# cyclops_r2b.net
KiCad netlist of a schematic drawn in EAGLE
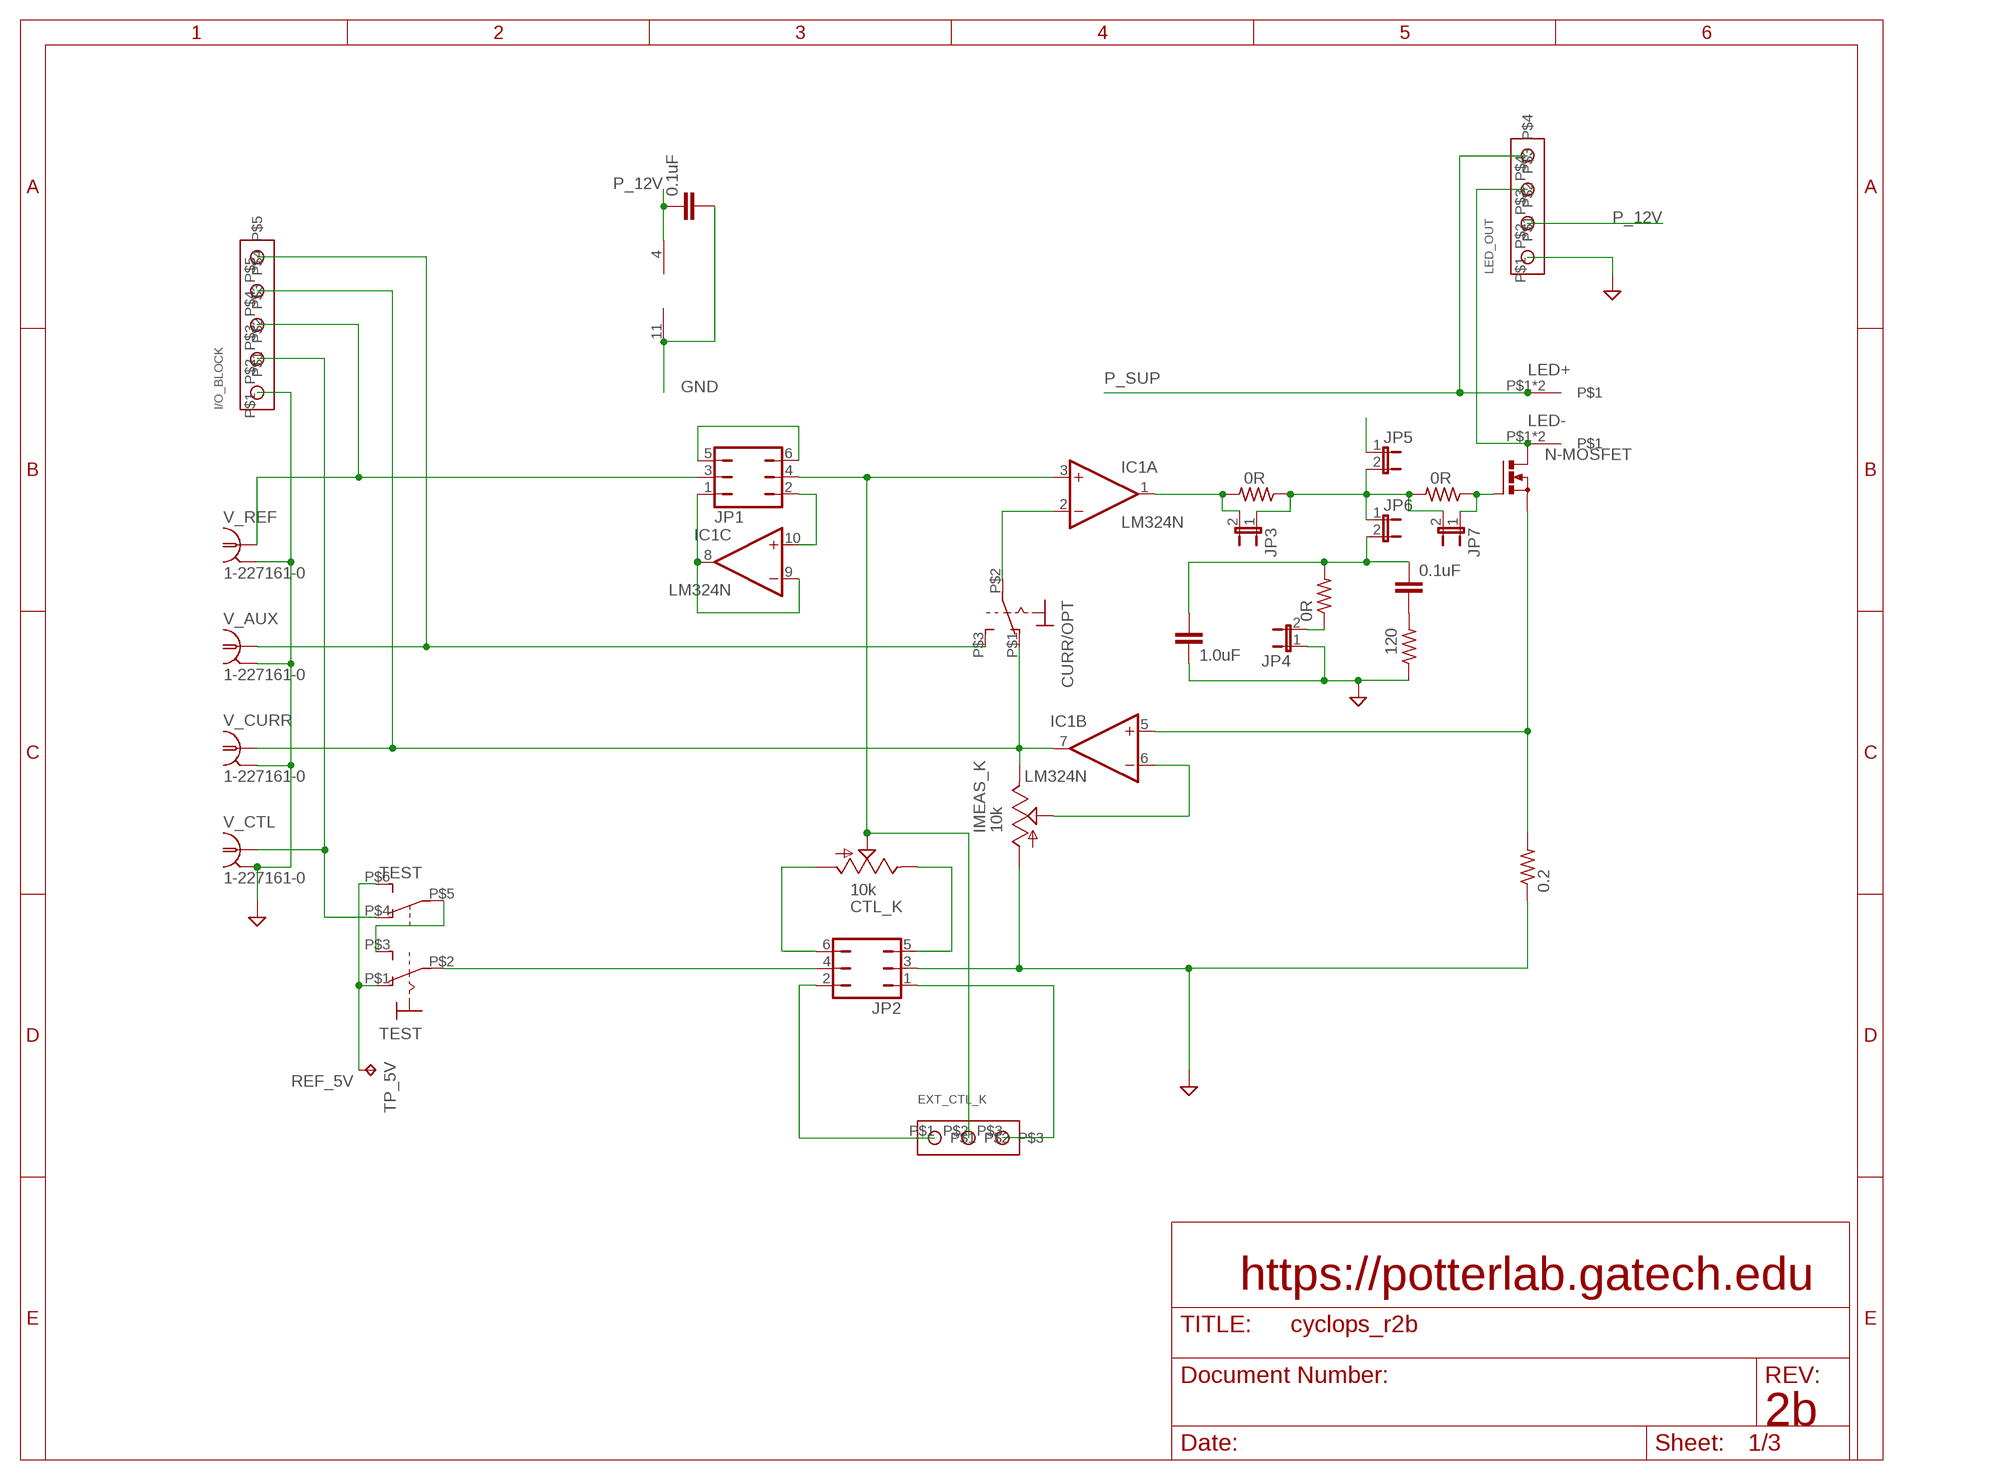
[diagram p0: schematic, sheet 1]
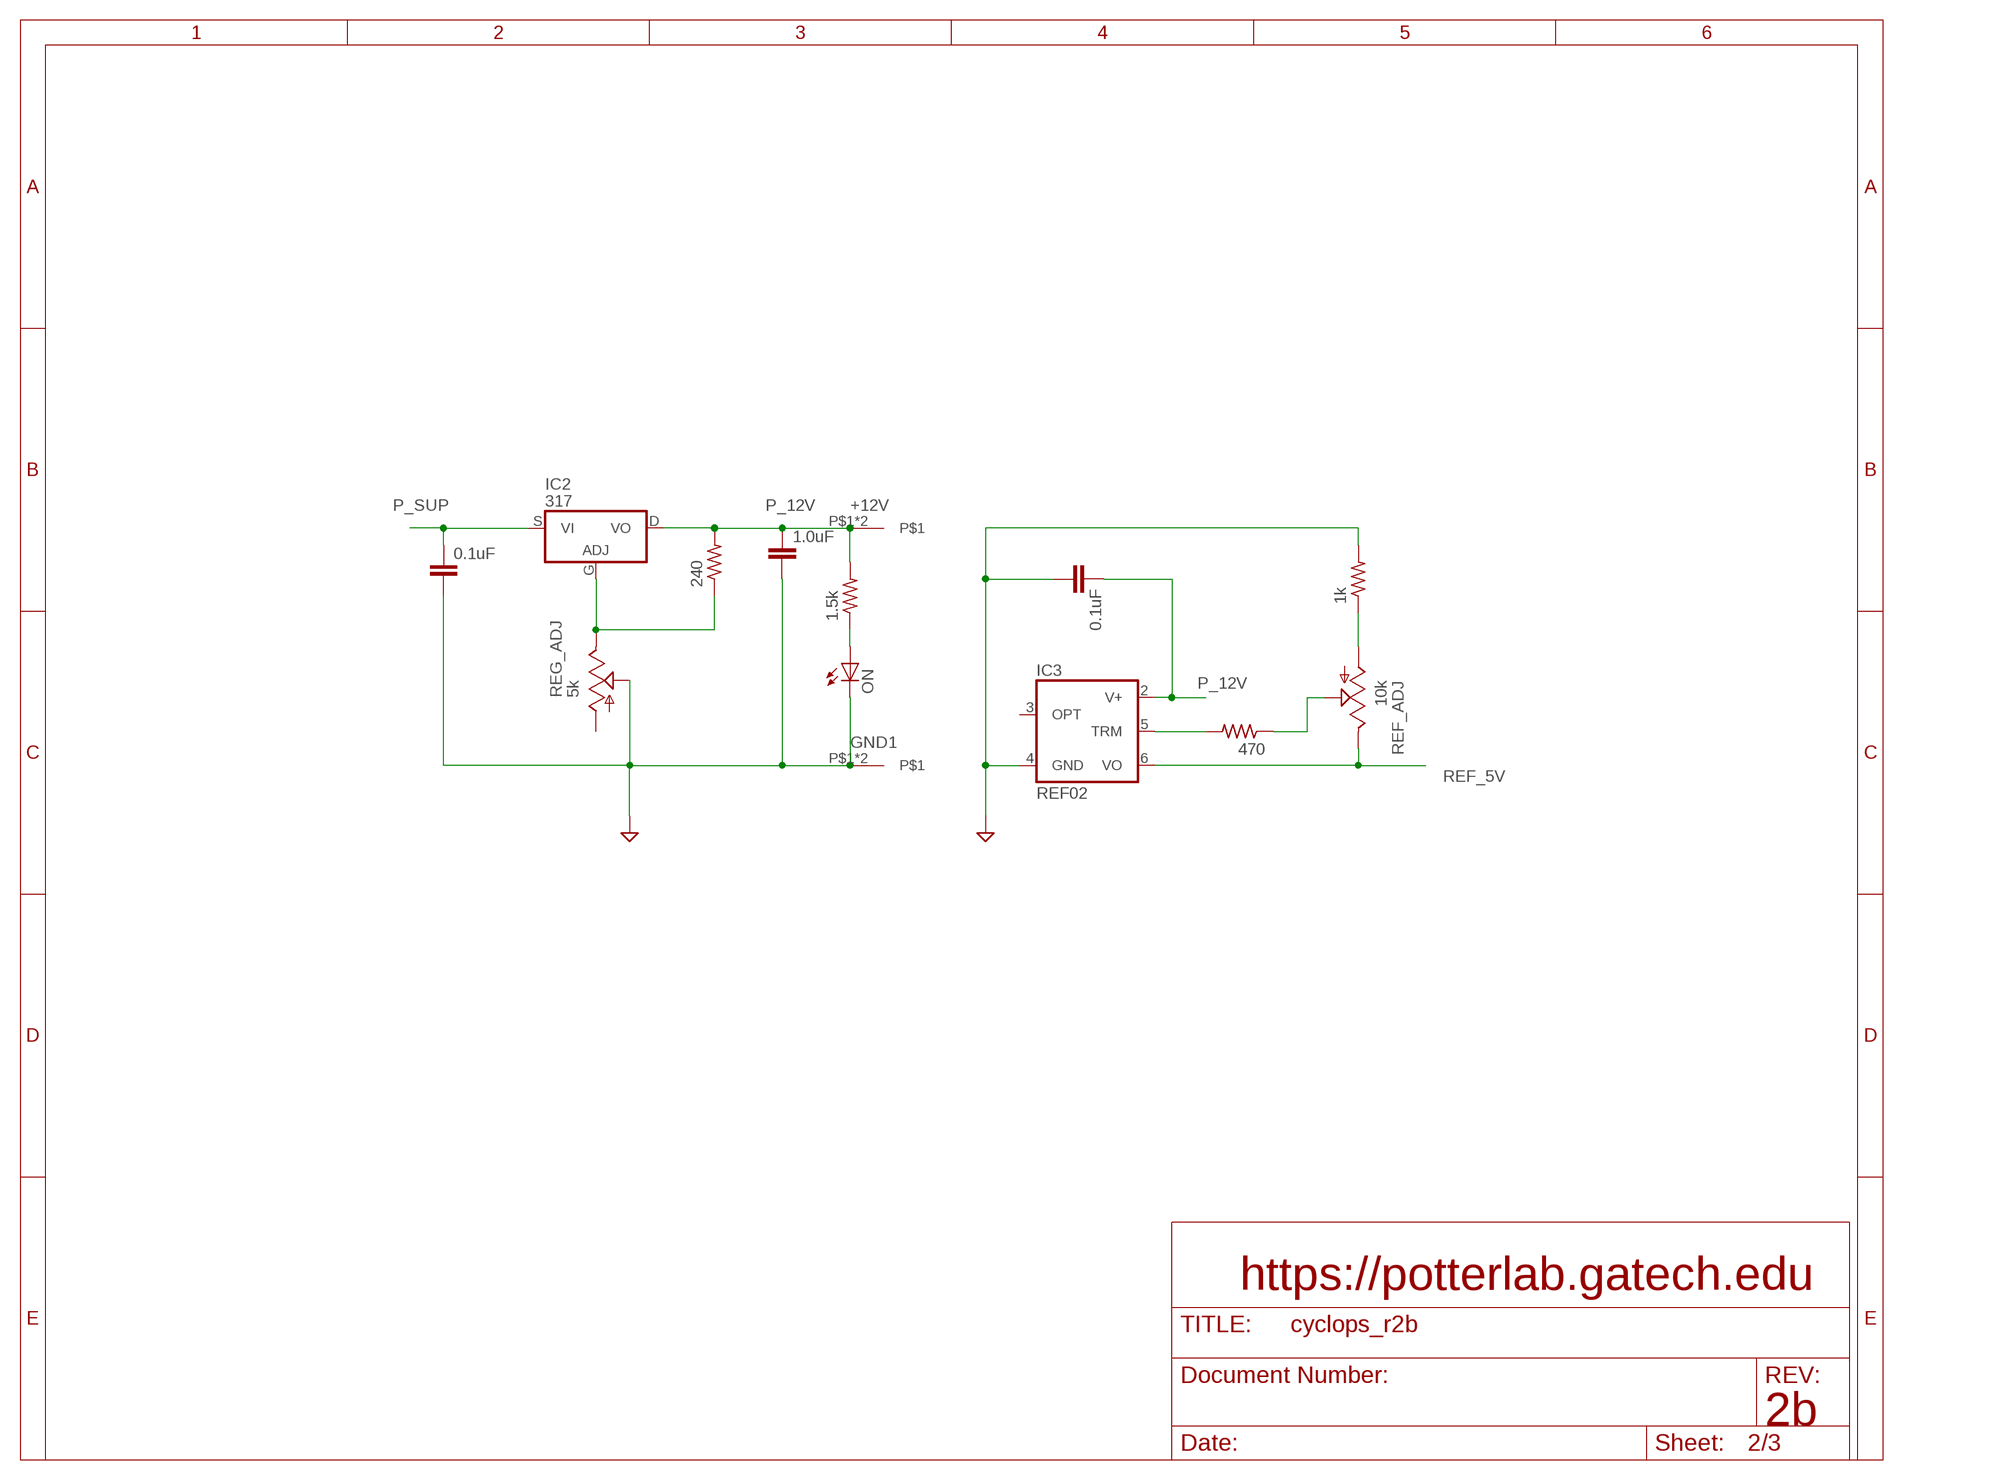
[diagram p1: schematic, sheet 2]
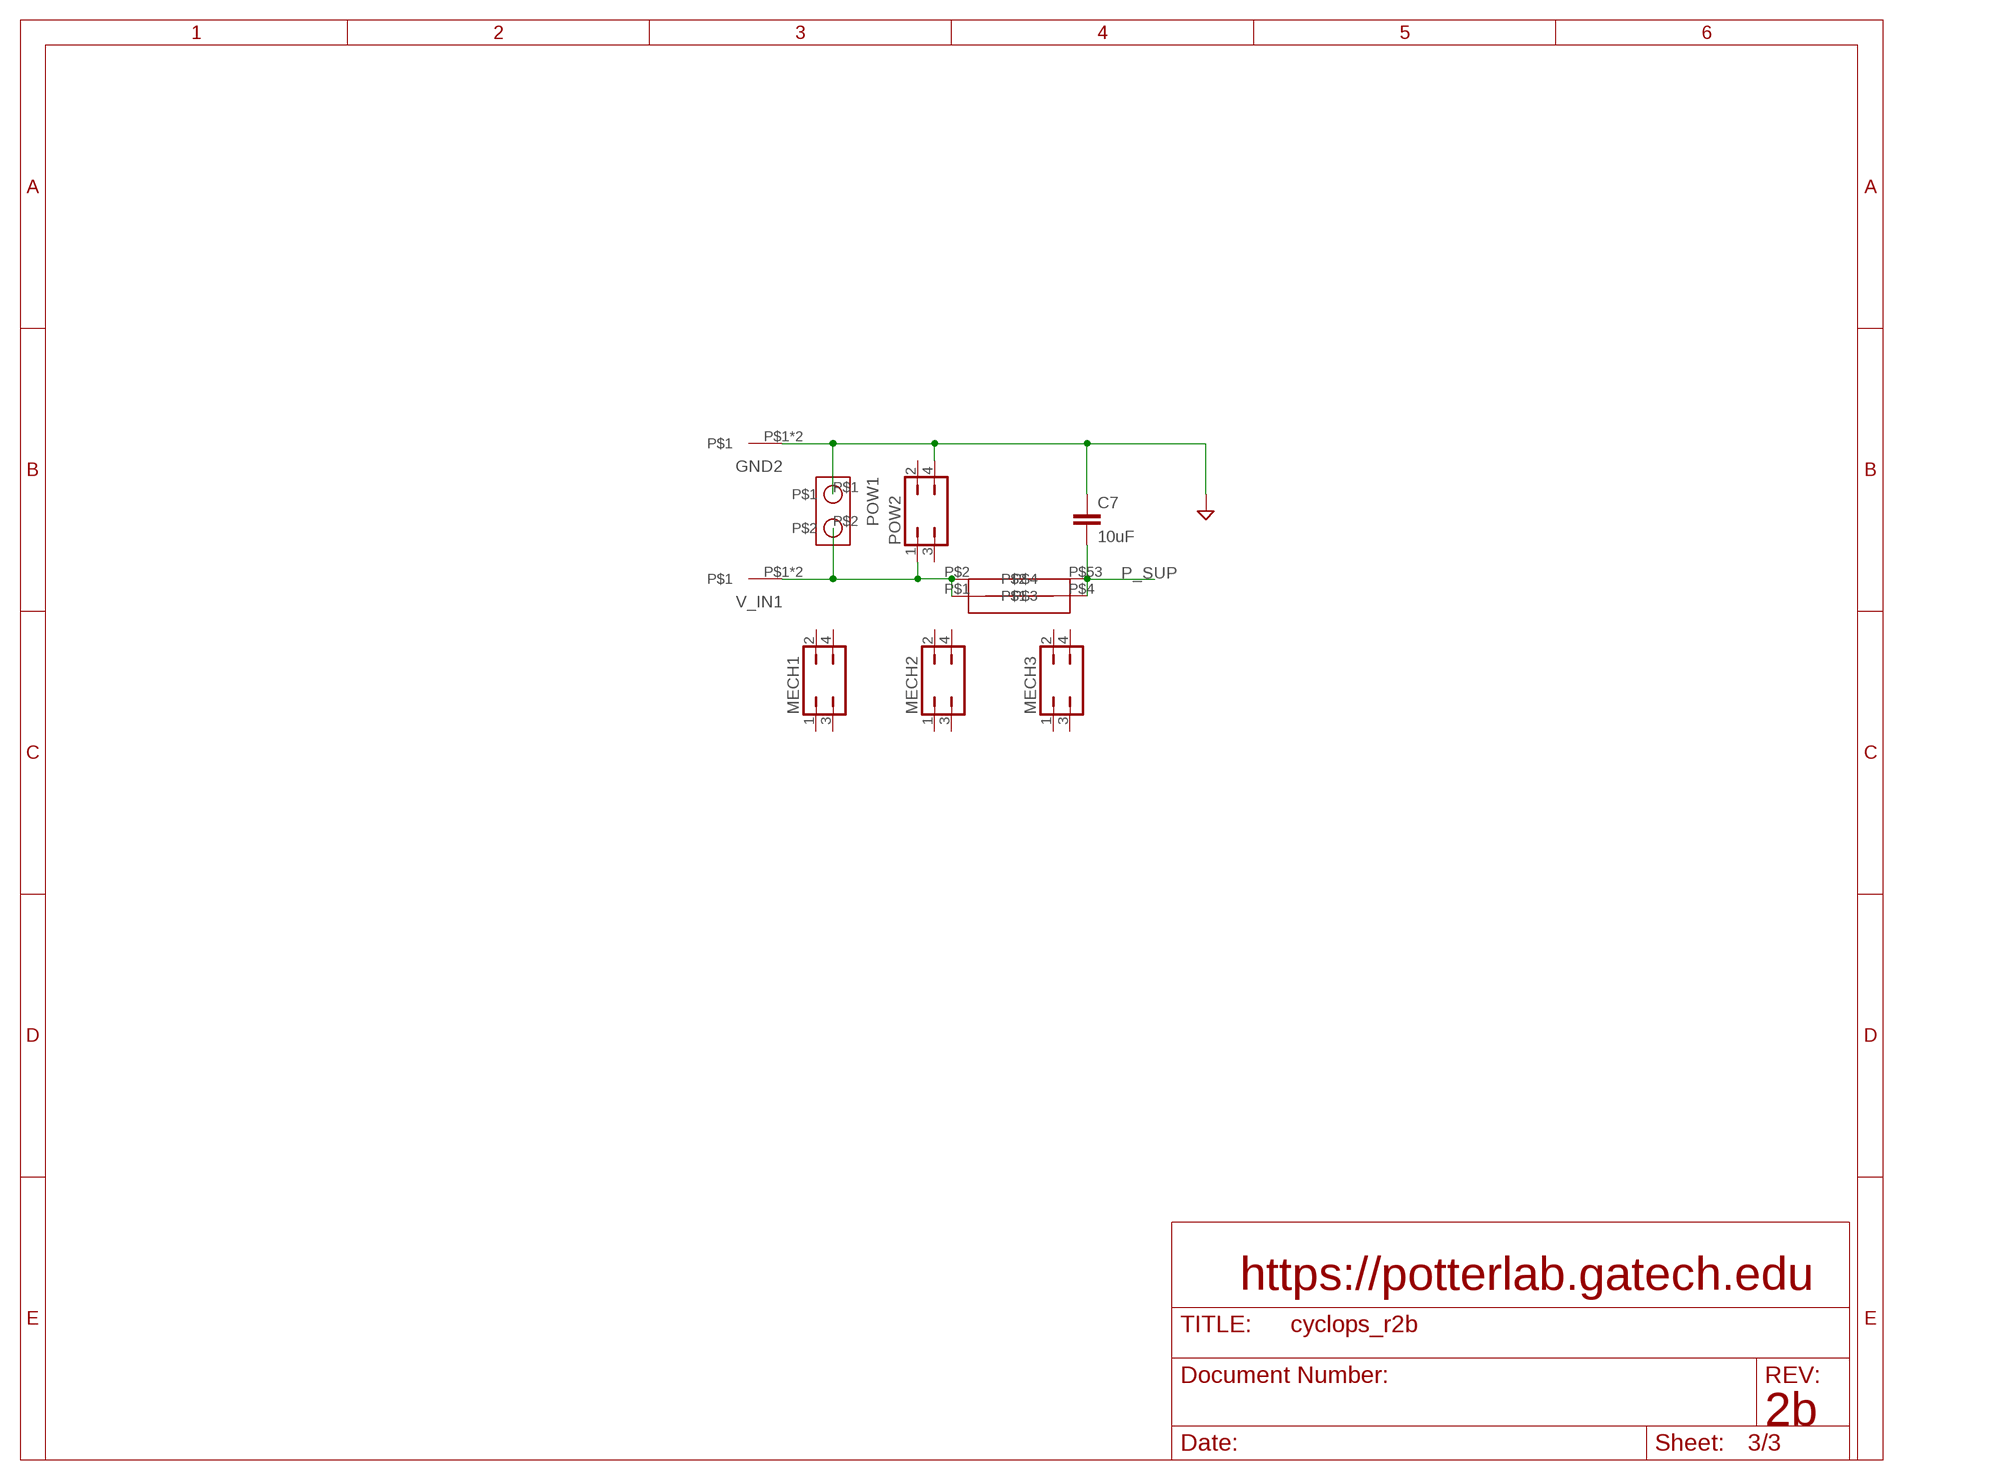
[diagram p2: schematic, sheet 3]

(export (version "E")
  (design (tool "Eeschema 10.0.6"))
  (components
    (comp (ref "+12V")
      (value "BANANA_TO_BOARD")
      (footprint "eagle-import:BANANA_TO_BOARD")
      (libsource (lib "eagle-import") (part "BANANA_TO_BOARD"))
    )
    (comp (ref "C4")
      (value "0.1uF")
      (footprint "eagle-import:C050-024X044")
      (libsource (lib "eagle-import") (part "C-EU050-024X044"))
    )
    (comp (ref "C5")
      (value "1.0uF")
      (footprint "eagle-import:C025-024X044")
      (libsource (lib "eagle-import") (part "C-EU025-024X044"))
    )
    (comp (ref "C6")
      (value "0.1uF")
      (footprint "eagle-import:C050-024X044")
      (libsource (lib "eagle-import") (part "C-EU050-024X044"))
    )
    (comp (ref "GND1")
      (value "BANANA_TO_BOARD")
      (footprint "eagle-import:BANANA_TO_BOARD")
      (libsource (lib "eagle-import") (part "BANANA_TO_BOARD"))
    )
    (comp (ref "IC2")
      (value "317")
      (footprint "eagle-import:TO220BH")
      (libsource (lib "eagle-import") (part "317"))
    )
    (comp (ref "IC3")
      (value "REF02")
      (footprint "eagle-import:DIL08-OVAL")
      (libsource (lib "eagle-import") (part "REF02DIL08-LONG"))
    )
    (comp (ref "ON")
      (value "LED3MM")
      (footprint "eagle-import:LED3MM")
      (libsource (lib "eagle-import") (part "LED3MM"))
    )
    (comp (ref "R5")
      (value "240")
      (footprint "eagle-import:0207_7")
      (libsource (lib "eagle-import") (part "R-US_0207/7"))
    )
    (comp (ref "R6")
      (value "1.5k")
      (footprint "eagle-import:0207_7")
      (libsource (lib "eagle-import") (part "R-US_0207/7"))
    )
    (comp (ref "R7")
      (value "470")
      (footprint "eagle-import:0207_7")
      (libsource (lib "eagle-import") (part "R-US_0207/7"))
    )
    (comp (ref "R8")
      (value "1k")
      (footprint "eagle-import:0207_7")
      (libsource (lib "eagle-import") (part "R-US_0207/7"))
    )
    (comp (ref "REF_ADJ")
      (value "10k")
      (footprint "eagle-import:RJ6S")
      (libsource (lib "eagle-import") (part "TRIM_US-RJ6S"))
    )
    (comp (ref "REG_ADJ")
      (value "5k")
      (footprint "eagle-import:RJ6S")
      (libsource (lib "eagle-import") (part "TRIM_US-RJ6S"))
    )
    (comp (ref "C7")
      (value "10uF")
      (footprint "eagle-import:C025-024X044")
      (libsource (lib "eagle-import") (part "C-EU025-024X044"))
    )
    (comp (ref "GND2")
      (value "BANANA_TO_BOARD")
      (footprint "eagle-import:BANANA_TO_BOARD")
      (libsource (lib "eagle-import") (part "BANANA_TO_BOARD"))
    )
    (comp (ref "MECH1")
      (value "JP2Q")
      (footprint "eagle-import:JP2Q")
      (libsource (lib "eagle-import") (part "JP2Q"))
    )
    (comp (ref "MECH2")
      (value "JP2Q")
      (footprint "eagle-import:JP2Q")
      (libsource (lib "eagle-import") (part "JP2Q"))
    )
    (comp (ref "MECH3")
      (value "JP2Q")
      (footprint "eagle-import:JP2Q")
      (libsource (lib "eagle-import") (part "JP2Q"))
    )
    (comp (ref "POW1")
      (value "SCREW2")
      (footprint "eagle-import:SCREW2")
      (libsource (lib "eagle-import") (part "SCREW2"))
    )
    (comp (ref "POW2")
      (value "JP2Q")
      (footprint "eagle-import:JP2Q")
      (libsource (lib "eagle-import") (part "JP2Q"))
    )
    (comp (ref "U$1")
      (value "FUSE >2A")
      (footprint "eagle-import:NXT-FUSE")
      (libsource (lib "eagle-import") (part "NXT-FUSE"))
    )
    (comp (ref "V_IN1")
      (value "BANANA_TO_BOARD")
      (footprint "eagle-import:BANANA_TO_BOARD")
      (libsource (lib "eagle-import") (part "BANANA_TO_BOARD"))
    )
    (comp (ref "C1")
      (value "0.1uF")
      (footprint "eagle-import:C050-024X044")
      (libsource (lib "eagle-import") (part "C-EU050-024X044"))
    )
    (comp (ref "C2")
      (value "1.0uF")
      (footprint "eagle-import:C025-024X044")
      (libsource (lib "eagle-import") (part "C-EU025-024X044"))
    )
    (comp (ref "C3")
      (value "0.1uF")
      (footprint "eagle-import:C050-024X044")
      (libsource (lib "eagle-import") (part "C-EU050-024X044"))
    )
    (comp (ref "CTL_K")
      (value "10k")
      (footprint "eagle-import:RJ6S")
      (libsource (lib "eagle-import") (part "TRIM_US-RJ6S"))
    )
    (comp (ref "CURR/OPT")
      (value "SPST_SWITCH")
      (footprint "eagle-import:A_TOGGLE_SPST")
      (libsource (lib "eagle-import") (part "SPST_SWITCH"))
    )
    (comp (ref "EXT_CTL_K")
      (value "SCREW3")
      (footprint "eagle-import:SCREW3")
      (libsource (lib "eagle-import") (part "SCREW3"))
    )
    (comp (ref "I/O_BLOCK")
      (value "SCREW5")
      (footprint "eagle-import:SCREW5")
      (libsource (lib "eagle-import") (part "SCREW5"))
    )
    (comp (ref "IC1")
      (value "LM324N")
      (footprint "eagle-import:DIL14")
      (libsource (lib "eagle-import") (part "LM324N"))
    )
    (comp (ref "IMEAS_K")
      (value "10k")
      (footprint "eagle-import:RJ6S")
      (libsource (lib "eagle-import") (part "TRIM_US-RJ6S"))
    )
    (comp (ref "JP1")
      (value "JP3Q")
      (footprint "eagle-import:JP3Q")
      (libsource (lib "eagle-import") (part "JP3Q"))
    )
    (comp (ref "JP2")
      (value "JP3Q")
      (footprint "eagle-import:JP3Q")
      (libsource (lib "eagle-import") (part "JP3Q"))
    )
    (comp (ref "JP3")
      (value "JP1E")
      (footprint "eagle-import:JP1")
      (libsource (lib "eagle-import") (part "JP1E"))
    )
    (comp (ref "JP4")
      (value "JP1E")
      (footprint "eagle-import:JP1")
      (libsource (lib "eagle-import") (part "JP1E"))
    )
    (comp (ref "JP5")
      (value "JP1E")
      (footprint "eagle-import:JP1")
      (libsource (lib "eagle-import") (part "JP1E"))
    )
    (comp (ref "JP6")
      (value "JP1E")
      (footprint "eagle-import:JP1")
      (libsource (lib "eagle-import") (part "JP1E"))
    )
    (comp (ref "JP7")
      (value "JP1E")
      (footprint "eagle-import:JP1")
      (libsource (lib "eagle-import") (part "JP1E"))
    )
    (comp (ref "LED+")
      (value "BANANA_TO_BOARD")
      (footprint "eagle-import:BANANA_TO_BOARD")
      (libsource (lib "eagle-import") (part "BANANA_TO_BOARD"))
    )
    (comp (ref "LED-")
      (value "BANANA_TO_BOARD")
      (footprint "eagle-import:BANANA_TO_BOARD")
      (libsource (lib "eagle-import") (part "BANANA_TO_BOARD"))
    )
    (comp (ref "LED_OUT")
      (value "SCREW4")
      (footprint "eagle-import:SCREW4")
      (libsource (lib "eagle-import") (part "SCREW4"))
    )
    (comp (ref "N-MOSFET")
      (value "PMOSFET_NTO220BH")
      (footprint "eagle-import:TO220BH")
      (libsource (lib "eagle-import") (part "PMOSFET_NTO220BH"))
    )
    (comp (ref "R1")
      (value "0R")
      (footprint "eagle-import:0207_7")
      (libsource (lib "eagle-import") (part "R-US_0207/7"))
    )
    (comp (ref "R2")
      (value "0R")
      (footprint "eagle-import:0207_7")
      (libsource (lib "eagle-import") (part "R-US_0207/7"))
    )
    (comp (ref "R3")
      (value "120")
      (footprint "eagle-import:0207_7")
      (libsource (lib "eagle-import") (part "R-US_0207/7"))
    )
    (comp (ref "R4")
      (value "0R")
      (footprint "eagle-import:0207_7")
      (libsource (lib "eagle-import") (part "R-US_0207/7"))
    )
    (comp (ref "R_CURR")
      (value "0.2")
      (footprint "eagle-import:IMEAS_R")
      (libsource (lib "eagle-import") (part "cyclops_R-US_0617/22"))
    )
    (comp (ref "TEST")
      (value "SP3T_SWITCH")
      (footprint "eagle-import:320-938")
      (libsource (lib "eagle-import") (part "SP3T_SWITCH"))
    )
    (comp (ref "TP_5V")
      (value "TPPAD1-13")
      (footprint "eagle-import:P1-13")
      (libsource (lib "eagle-import") (part "TPPAD1-13"))
    )
    (comp (ref "V_AUX")
      (value "1-227161-0")
      (footprint "eagle-import:AMP_227161")
      (libsource (lib "eagle-import") (part "?2271611--0"))
    )
    (comp (ref "V_CTL")
      (value "1-227161-0")
      (footprint "eagle-import:AMP_227161")
      (libsource (lib "eagle-import") (part "?2271611--0"))
    )
    (comp (ref "V_CURR")
      (value "1-227161-0")
      (footprint "eagle-import:AMP_227161")
      (libsource (lib "eagle-import") (part "?2271611--0"))
    )
    (comp (ref "V_REF")
      (value "1-227161-0")
      (footprint "eagle-import:AMP_227161")
      (libsource (lib "eagle-import") (part "?2271611--0"))
    )
  )
  (nets
    (net (code "1") (name "GND") (class "Default")
      (node (ref "C1") (pin "2") (pinfunction "2_2") (pintype "passive"))
      (node (ref "C2") (pin "2") (pinfunction "2_2") (pintype "passive"))
      (node (ref "C4") (pin "2") (pinfunction "2_2") (pintype "passive"))
      (node (ref "C5") (pin "2") (pinfunction "2_2") (pintype "passive"))
      (node (ref "C6") (pin "2") (pinfunction "2_2") (pintype "passive"))
      (node (ref "C7") (pin "1") (pinfunction "1_1") (pintype "passive"))
      (node (ref "GND1") (pin "P$1") (pinfunction "P$1_P$1") (pintype "bidirectional"))
      (node (ref "GND1") (pin "P$2") (pinfunction "P$1_P$2") (pintype "bidirectional"))
      (node (ref "GND2") (pin "P$1") (pinfunction "P$1_P$1") (pintype "bidirectional"))
      (node (ref "GND2") (pin "P$2") (pinfunction "P$1_P$2") (pintype "bidirectional"))
      (node (ref "I/O_BLOCK") (pin "P$1") (pinfunction "P$1_P$1") (pintype "bidirectional"))
      (node (ref "IC1") (pin "11") (pinfunction "V-_11") (pintype "power_in"))
      (node (ref "IC3") (pin "4") (pinfunction "GND_4") (pintype "power_in"))
      (node (ref "IMEAS_K") (pin "A") (pinfunction "A_A") (pintype "passive"))
      (node (ref "JP2") (pin "3") (pinfunction "3_3") (pintype "passive"))
      (node (ref "JP4") (pin "1") (pinfunction "1_1") (pintype "passive"))
      (node (ref "LED_OUT") (pin "P$1") (pinfunction "P$1_P$1") (pintype "bidirectional"))
      (node (ref "ON") (pin "K") (pinfunction "C_K") (pintype "passive"))
      (node (ref "POW1") (pin "P$1") (pinfunction "P$1_P$1") (pintype "bidirectional"))
      (node (ref "POW2") (pin "4") (pinfunction "4_4") (pintype "passive"))
      (node (ref "R3") (pin "1") (pinfunction "1_1") (pintype "passive"))
      (node (ref "R8") (pin "2") (pinfunction "2_2") (pintype "passive"))
      (node (ref "REG_ADJ") (pin "S") (pinfunction "S_S") (pintype "passive"))
      (node (ref "R_CURR") (pin "1") (pinfunction "1_1") (pintype "passive"))
      (node (ref "V_AUX") (pin "2") (pinfunction "GND_2") (pintype "power_in"))
      (node (ref "V_CTL") (pin "2") (pinfunction "GND_2") (pintype "power_in"))
      (node (ref "V_CURR") (pin "2") (pinfunction "GND_2") (pintype "power_in"))
      (node (ref "V_REF") (pin "2") (pinfunction "GND_2") (pintype "power_in"))
    )
    (net (code "2") (name "Net-(C2-Pad1)") (class "Default")
      (node (ref "C2") (pin "1") (pinfunction "1_1") (pintype "passive"))
      (node (ref "C3") (pin "1") (pinfunction "1_1") (pintype "passive"))
      (node (ref "JP6") (pin "2") (pinfunction "2_2") (pintype "passive"))
      (node (ref "R2") (pin "2") (pinfunction "2_2") (pintype "passive"))
    )
    (net (code "3") (name "Net-(C3-Pad2)") (class "Default")
      (node (ref "C3") (pin "2") (pinfunction "2_2") (pintype "passive"))
      (node (ref "R3") (pin "2") (pinfunction "2_2") (pintype "passive"))
    )
    (net (code "4") (name "Net-(CTL_K-PadA)") (class "Default")
      (node (ref "CTL_K") (pin "A") (pinfunction "A_A") (pintype "passive"))
      (node (ref "JP2") (pin "6") (pinfunction "6_6") (pintype "passive"))
    )
    (net (code "5") (name "Net-(CTL_K-PadE)") (class "Default")
      (node (ref "CTL_K") (pin "E") (pinfunction "E_E") (pintype "passive"))
      (node (ref "JP2") (pin "5") (pinfunction "5_5") (pintype "passive"))
    )
    (net (code "6") (name "Net-(CURR/OPT-O)") (class "Default")
      (node (ref "CURR/OPT") (pin "P$1") (pinfunction "O_P$1") (pintype "passive"))
      (node (ref "I/O_BLOCK") (pin "P$4") (pinfunction "P$4_P$4") (pintype "bidirectional"))
      (node (ref "IC1") (pin "7") (pinfunction "OUT_7") (pintype "output"))
      (node (ref "IMEAS_K") (pin "E") (pinfunction "E_E") (pintype "passive"))
      (node (ref "V_CURR") (pin "1") (pinfunction "1_1") (pintype "passive"))
    )
    (net (code "7") (name "Net-(CURR/OPT-P)") (class "Default")
      (node (ref "CURR/OPT") (pin "P$2") (pinfunction "P_P$2") (pintype "passive"))
      (node (ref "IC1") (pin "2") (pinfunction "-IN_2") (pintype "input"))
    )
    (net (code "8") (name "Net-(CURR/OPT-S)") (class "Default")
      (node (ref "CURR/OPT") (pin "P$3") (pinfunction "S_P$3") (pintype "passive"))
      (node (ref "I/O_BLOCK") (pin "P$5") (pinfunction "P$5_P$5") (pintype "bidirectional"))
      (node (ref "V_AUX") (pin "1") (pinfunction "1_1") (pintype "passive"))
    )
    (net (code "9") (name "Net-(EXT_CTL_K-PadP$1)") (class "Default")
      (node (ref "EXT_CTL_K") (pin "P$1") (pinfunction "P$1_P$1") (pintype "bidirectional"))
      (node (ref "JP2") (pin "2") (pinfunction "2_2") (pintype "passive"))
    )
    (net (code "10") (name "Net-(EXT_CTL_K-PadP$3)") (class "Default")
      (node (ref "EXT_CTL_K") (pin "P$3") (pinfunction "P$3_P$3") (pintype "bidirectional"))
      (node (ref "JP2") (pin "1") (pinfunction "1_1") (pintype "passive"))
    )
    (net (code "11") (name "Net-(I/O_BLOCK-PadP$3)") (class "Default")
      (node (ref "I/O_BLOCK") (pin "P$3") (pinfunction "P$3_P$3") (pintype "bidirectional"))
      (node (ref "JP1") (pin "3") (pinfunction "3_3") (pintype "passive"))
      (node (ref "V_REF") (pin "1") (pinfunction "1_1") (pintype "passive"))
    )
    (net (code "12") (name "Net-(IC1A-+IN)") (class "Default")
      (node (ref "CTL_K") (pin "S") (pinfunction "S_S") (pintype "passive"))
      (node (ref "EXT_CTL_K") (pin "P$2") (pinfunction "P$2_P$2") (pintype "bidirectional"))
      (node (ref "IC1") (pin "3") (pinfunction "+IN_3") (pintype "input"))
      (node (ref "JP1") (pin "4") (pinfunction "4_4") (pintype "passive"))
    )
    (net (code "13") (name "Net-(IC1A-OUT)") (class "Default")
      (node (ref "IC1") (pin "1") (pinfunction "OUT_1") (pintype "output"))
      (node (ref "JP3") (pin "2") (pinfunction "2_2") (pintype "passive"))
      (node (ref "R1") (pin "2") (pinfunction "2_2") (pintype "passive"))
    )
    (net (code "14") (name "Net-(IC1B-+IN)") (class "Default")
      (node (ref "IC1") (pin "5") (pinfunction "+IN_5") (pintype "input"))
      (node (ref "N-MOSFET") (pin "S") (pinfunction "S_S") (pintype "passive"))
      (node (ref "R_CURR") (pin "2") (pinfunction "2_2") (pintype "passive"))
    )
    (net (code "15") (name "Net-(IC1B--IN)") (class "Default")
      (node (ref "IC1") (pin "6") (pinfunction "-IN_6") (pintype "input"))
      (node (ref "IMEAS_K") (pin "S") (pinfunction "S_S") (pintype "passive"))
    )
    (net (code "16") (name "Net-(IC1C-+IN)") (class "Default")
      (node (ref "IC1") (pin "10") (pinfunction "+IN_10") (pintype "input"))
      (node (ref "JP1") (pin "2") (pinfunction "2_2") (pintype "passive"))
    )
    (net (code "17") (name "Net-(IC1C--IN)") (class "Default")
      (node (ref "IC1") (pin "8") (pinfunction "OUT_8") (pintype "output"))
      (node (ref "IC1") (pin "9") (pinfunction "-IN_9") (pintype "input"))
      (node (ref "JP1") (pin "1") (pinfunction "1_1") (pintype "passive"))
    )
    (net (code "18") (name "Net-(IC2-ADJ)") (class "Default")
      (node (ref "IC2") (pin "G") (pinfunction "ADJ_G") (pintype "input"))
      (node (ref "R5") (pin "1") (pinfunction "1_1") (pintype "passive"))
      (node (ref "REG_ADJ") (pin "E") (pinfunction "E_E") (pintype "passive"))
    )
    (net (code "19") (name "Net-(IC3-TRM)") (class "Default")
      (node (ref "IC3") (pin "5") (pinfunction "TRM_5") (pintype "input"))
      (node (ref "R7") (pin "2") (pinfunction "2_2") (pintype "passive"))
    )
    (net (code "20") (name "Net-(JP1-Pad5)") (class "Default")
      (node (ref "JP1") (pin "5") (pinfunction "5_5") (pintype "passive"))
      (node (ref "JP1") (pin "6") (pinfunction "6_6") (pintype "passive"))
    )
    (net (code "21") (name "Net-(JP3-Pad1)") (class "Default")
      (node (ref "JP3") (pin "1") (pinfunction "1_1") (pintype "passive"))
      (node (ref "JP5") (pin "2") (pinfunction "2_2") (pintype "passive"))
      (node (ref "JP6") (pin "1") (pinfunction "1_1") (pintype "passive"))
      (node (ref "JP7") (pin "2") (pinfunction "2_2") (pintype "passive"))
      (node (ref "R1") (pin "1") (pinfunction "1_1") (pintype "passive"))
      (node (ref "R4") (pin "2") (pinfunction "2_2") (pintype "passive"))
    )
    (net (code "22") (name "Net-(JP4-Pad2)") (class "Default")
      (node (ref "JP4") (pin "2") (pinfunction "2_2") (pintype "passive"))
      (node (ref "R2") (pin "1") (pinfunction "1_1") (pintype "passive"))
    )
    (net (code "23") (name "Net-(JP7-Pad1)") (class "Default")
      (node (ref "JP7") (pin "1") (pinfunction "1_1") (pintype "passive"))
      (node (ref "N-MOSFET") (pin "G") (pinfunction "G_G") (pintype "passive"))
      (node (ref "R4") (pin "1") (pinfunction "1_1") (pintype "passive"))
    )
    (net (code "24") (name "Net-(LED--P$1-PadP$2)") (class "Default")
      (node (ref "LED-") (pin "P$1") (pinfunction "P$1_P$1") (pintype "bidirectional"))
      (node (ref "LED-") (pin "P$2") (pinfunction "P$1_P$2") (pintype "bidirectional"))
      (node (ref "LED_OUT") (pin "P$3") (pinfunction "P$3_P$3") (pintype "bidirectional"))
      (node (ref "N-MOSFET") (pin "D") (pinfunction "D_D") (pintype "passive"))
    )
    (net (code "25") (name "Net-(ON-PadA)") (class "Default")
      (node (ref "ON") (pin "A") (pinfunction "A_A") (pintype "passive"))
      (node (ref "R6") (pin "1") (pinfunction "1_1") (pintype "passive"))
    )
    (net (code "26") (name "Net-(POW1-PadP$2)") (class "Default")
      (node (ref "POW1") (pin "P$2") (pinfunction "P$2_P$2") (pintype "bidirectional"))
      (node (ref "POW2") (pin "1") (pinfunction "1_1") (pintype "passive"))
      (node (ref "U$1") (pin "P$1") (pinfunction "P$1_P$1") (pintype "bidirectional"))
      (node (ref "U$1") (pin "P$2") (pinfunction "P$2_P$2") (pintype "bidirectional"))
      (node (ref "V_IN1") (pin "P$1") (pinfunction "P$1_P$1") (pintype "bidirectional"))
      (node (ref "V_IN1") (pin "P$2") (pinfunction "P$1_P$2") (pintype "bidirectional"))
    )
    (net (code "27") (name "Net-(R7-Pad1)") (class "Default")
      (node (ref "R7") (pin "1") (pinfunction "1_1") (pintype "passive"))
      (node (ref "REF_ADJ") (pin "S") (pinfunction "S_S") (pintype "passive"))
    )
    (net (code "28") (name "Net-(R8-Pad1)") (class "Default")
      (node (ref "R8") (pin "1") (pinfunction "1_1") (pintype "passive"))
      (node (ref "REF_ADJ") (pin "A") (pinfunction "A_A") (pintype "passive"))
    )
    (net (code "29") (name "Net-(TESTA-P)") (class "Default")
      (node (ref "JP2") (pin "4") (pinfunction "4_4") (pintype "passive"))
      (node (ref "TEST") (pin "P$2") (pinfunction "P_P$2") (pintype "passive"))
    )
    (net (code "30") (name "Net-(TESTA-S)") (class "Default")
      (node (ref "TEST") (pin "P$3") (pinfunction "S_P$3") (pintype "passive"))
      (node (ref "TEST") (pin "P$5") (pinfunction "P_P$5") (pintype "passive"))
    )
    (net (code "31") (name "Net-(TESTB-O)") (class "Default")
      (node (ref "I/O_BLOCK") (pin "P$2") (pinfunction "P$2_P$2") (pintype "bidirectional"))
      (node (ref "TEST") (pin "P$4") (pinfunction "O_P$4") (pintype "passive"))
      (node (ref "V_CTL") (pin "1") (pinfunction "1_1") (pintype "passive"))
    )
    (net (code "32") (name "P_12V") (class "Default")
      (node (ref "+12V") (pin "P$1") (pinfunction "P$1_P$1") (pintype "bidirectional"))
      (node (ref "+12V") (pin "P$2") (pinfunction "P$1_P$2") (pintype "bidirectional"))
      (node (ref "C1") (pin "1") (pinfunction "1_1") (pintype "passive"))
      (node (ref "C5") (pin "1") (pinfunction "1_1") (pintype "passive"))
      (node (ref "C6") (pin "1") (pinfunction "1_1") (pintype "passive"))
      (node (ref "IC1") (pin "4") (pinfunction "V+_4") (pintype "power_in"))
      (node (ref "IC2") (pin "D") (pinfunction "VO_D") (pintype "passive"))
      (node (ref "IC3") (pin "2") (pinfunction "V+_2") (pintype "power_in"))
      (node (ref "LED_OUT") (pin "P$2") (pinfunction "P$2_P$2") (pintype "bidirectional"))
      (node (ref "R5") (pin "2") (pinfunction "2_2") (pintype "passive"))
      (node (ref "R6") (pin "2") (pinfunction "2_2") (pintype "passive"))
    )
    (net (code "33") (name "P_SUP") (class "Default")
      (node (ref "C4") (pin "1") (pinfunction "1_1") (pintype "passive"))
      (node (ref "C7") (pin "2") (pinfunction "2_2") (pintype "passive"))
      (node (ref "IC2") (pin "S") (pinfunction "VI_S") (pintype "input"))
      (node (ref "LED+") (pin "P$1") (pinfunction "P$1_P$1") (pintype "bidirectional"))
      (node (ref "LED+") (pin "P$2") (pinfunction "P$1_P$2") (pintype "bidirectional"))
      (node (ref "LED_OUT") (pin "P$4") (pinfunction "P$4_P$4") (pintype "bidirectional"))
      (node (ref "U$1") (pin "P$4") (pinfunction "P$3_P$4") (pintype "bidirectional"))
      (node (ref "U$1") (pin "P$53") (pinfunction "P$4_P$53") (pintype "bidirectional"))
    )
    (net (code "34") (name "REF_5V") (class "Default")
      (node (ref "IC3") (pin "6") (pinfunction "VO_6") (pintype "output"))
      (node (ref "REF_ADJ") (pin "E") (pinfunction "E_E") (pintype "passive"))
      (node (ref "TEST") (pin "P$1") (pinfunction "O_P$1") (pintype "passive"))
      (node (ref "TEST") (pin "P$6") (pinfunction "S_P$6") (pintype "passive"))
      (node (ref "TP_5V") (pin "TP") (pinfunction "TP_TP") (pintype "input"))
    )
    (net (code "35") (name "unconnected-(IC3-OPT-Pad3)") (class "Default")
      (node (ref "IC3") (pin "3") (pinfunction "OPT_3") (pintype "output"))
    )
    (net (code "36") (name "unconnected-(JP5-Pad1)") (class "Default")
      (node (ref "JP5") (pin "1") (pinfunction "1_1") (pintype "passive"))
    )
    (net (code "37") (name "unconnected-(MECH1-Pad1)") (class "Default")
      (node (ref "MECH1") (pin "1") (pinfunction "1_1") (pintype "passive"))
    )
    (net (code "38") (name "unconnected-(MECH1-Pad2)") (class "Default")
      (node (ref "MECH1") (pin "2") (pinfunction "2_2") (pintype "passive"))
    )
    (net (code "39") (name "unconnected-(MECH1-Pad3)") (class "Default")
      (node (ref "MECH1") (pin "3") (pinfunction "3_3") (pintype "passive"))
    )
    (net (code "40") (name "unconnected-(MECH1-Pad4)") (class "Default")
      (node (ref "MECH1") (pin "4") (pinfunction "4_4") (pintype "passive"))
    )
    (net (code "41") (name "unconnected-(MECH2-Pad1)") (class "Default")
      (node (ref "MECH2") (pin "1") (pinfunction "1_1") (pintype "passive"))
    )
    (net (code "42") (name "unconnected-(MECH2-Pad2)") (class "Default")
      (node (ref "MECH2") (pin "2") (pinfunction "2_2") (pintype "passive"))
    )
    (net (code "43") (name "unconnected-(MECH2-Pad3)") (class "Default")
      (node (ref "MECH2") (pin "3") (pinfunction "3_3") (pintype "passive"))
    )
    (net (code "44") (name "unconnected-(MECH2-Pad4)") (class "Default")
      (node (ref "MECH2") (pin "4") (pinfunction "4_4") (pintype "passive"))
    )
    (net (code "45") (name "unconnected-(MECH3-Pad1)") (class "Default")
      (node (ref "MECH3") (pin "1") (pinfunction "1_1") (pintype "passive"))
    )
    (net (code "46") (name "unconnected-(MECH3-Pad2)") (class "Default")
      (node (ref "MECH3") (pin "2") (pinfunction "2_2") (pintype "passive"))
    )
    (net (code "47") (name "unconnected-(MECH3-Pad3)") (class "Default")
      (node (ref "MECH3") (pin "3") (pinfunction "3_3") (pintype "passive"))
    )
    (net (code "48") (name "unconnected-(MECH3-Pad4)") (class "Default")
      (node (ref "MECH3") (pin "4") (pinfunction "4_4") (pintype "passive"))
    )
    (net (code "49") (name "unconnected-(POW2-Pad2)") (class "Default")
      (node (ref "POW2") (pin "2") (pinfunction "2_2") (pintype "passive"))
    )
    (net (code "50") (name "unconnected-(POW2-Pad3)") (class "Default")
      (node (ref "POW2") (pin "3") (pinfunction "3_3") (pintype "passive"))
    )
    (net (code "51") (name "unconnected-(REG_ADJ-PadA)") (class "Default")
      (node (ref "REG_ADJ") (pin "A") (pinfunction "A_A") (pintype "passive"))
    )
  )
)
